# altimeter.net
KiCad netlist of a schematic drawn in EAGLE
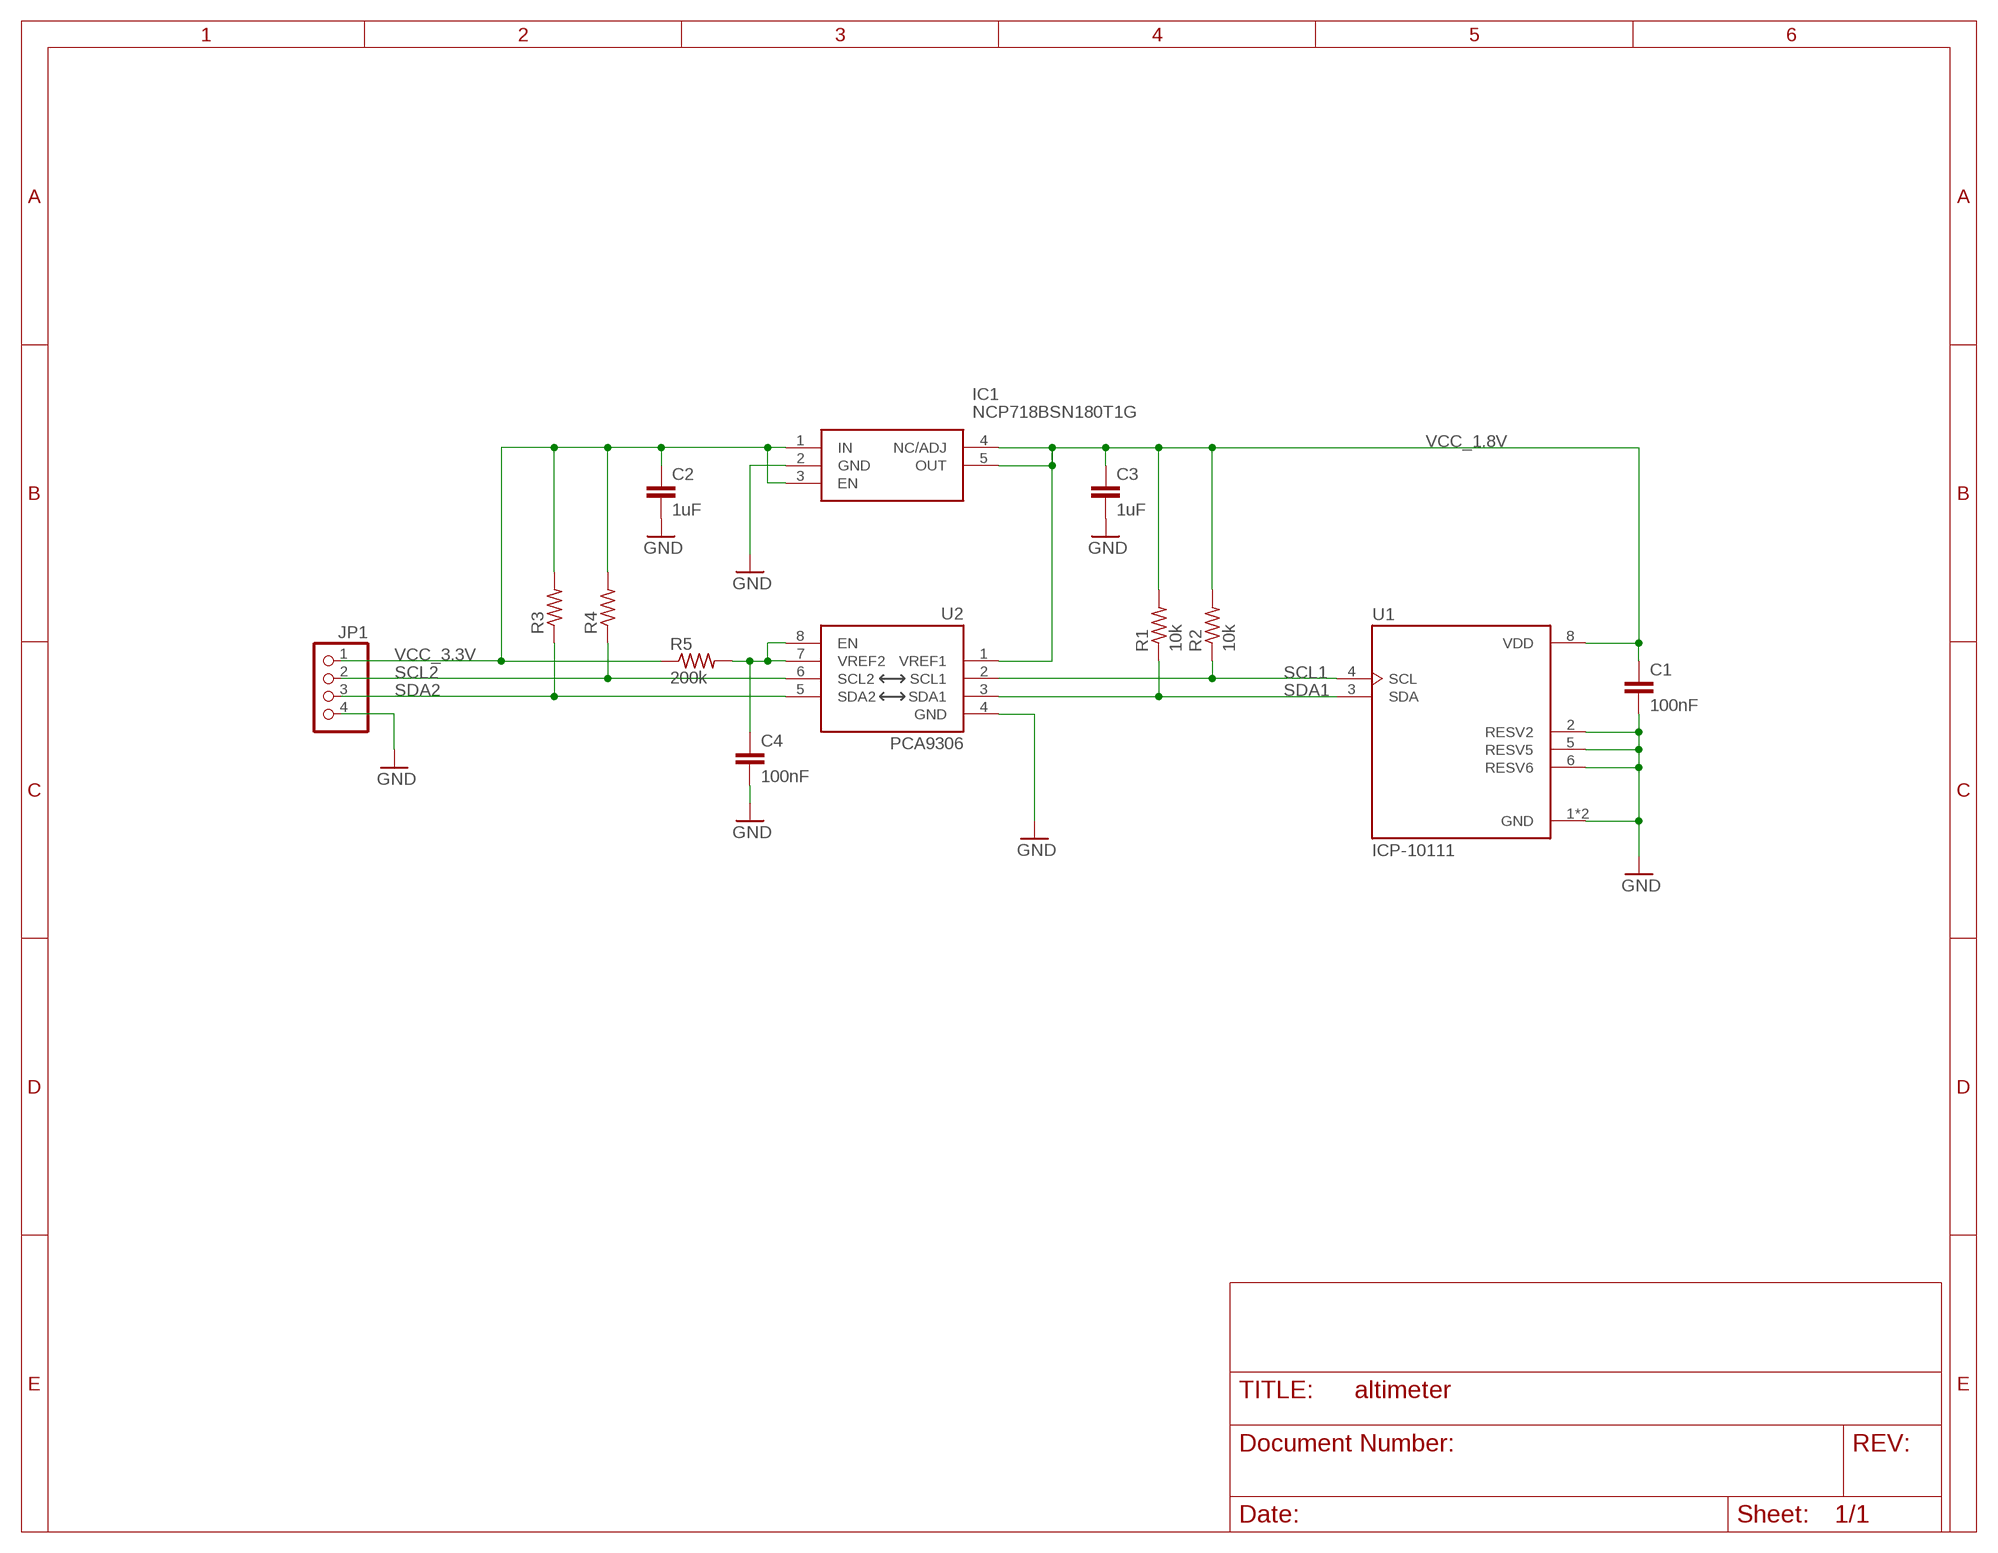
[diagram p0: schematic, sheet 1]

(export (version "E")
  (design (tool "Eeschema 10.0.6"))
  (components
    (comp (ref "C1")
      (value "100nF")
      (footprint "eagle-import:C0402")
      (libsource (lib "eagle-import") (part "C-EUC0402"))
    )
    (comp (ref "C2")
      (value "1uF")
      (footprint "eagle-import:C0402")
      (libsource (lib "eagle-import") (part "C-EUC0402"))
    )
    (comp (ref "C3")
      (value "1uF")
      (footprint "eagle-import:C0402")
      (libsource (lib "eagle-import") (part "C-EUC0402"))
    )
    (comp (ref "C4")
      (value "100nF")
      (footprint "eagle-import:C0402")
      (libsource (lib "eagle-import") (part "C-EUC0402"))
    )
    (comp (ref "IC1")
      (value "NCP718BSN180T1G")
      (footprint "eagle-import:SOT95P280X100-5N")
      (fields (field (name "MOUSER_PART_NUMBER") "863-NCP718BSN180T1G"))
      (libsource (lib "eagle-import") (part "NCP718BSN180T1G"))
    )
    (comp (ref "JP1")
      (value "PINHD-1X4")
      (footprint "eagle-import:1X04")
      (libsource (lib "eagle-import") (part "PINHD-1X4"))
    )
    (comp (ref "R1")
      (value "10k")
      (footprint "eagle-import:R0402")
      (libsource (lib "eagle-import") (part "R-US_R0402"))
    )
    (comp (ref "R2")
      (value "10k")
      (footprint "eagle-import:R0402")
      (libsource (lib "eagle-import") (part "R-US_R0402"))
    )
    (comp (ref "R3")
      (value "R-US_R0402")
      (footprint "eagle-import:R0402")
      (libsource (lib "eagle-import") (part "R-US_R0402"))
    )
    (comp (ref "R4")
      (value "R-US_R0402")
      (footprint "eagle-import:R0402")
      (libsource (lib "eagle-import") (part "R-US_R0402"))
    )
    (comp (ref "R5")
      (value "200k")
      (footprint "eagle-import:R0402")
      (libsource (lib "eagle-import") (part "R-US_R0402"))
    )
    (comp (ref "U1")
      (value "ICP-10111")
      (footprint "eagle-import:PSON65P250X200X100-8N")
      (fields (field (name "DIGI-KEY_PART_NUMBER") "1428-1145-1-ND") (field (name "MF") "TDK InvenSense"))
      (libsource (lib "eagle-import") (part "ICP-10111"))
    )
    (comp (ref "U2")
      (value "PCA9306")
      (footprint "eagle-import:PCA9306DC")
      (libsource (lib "eagle-import") (part "PCA9306PCA9306DC-1{colon}1"))
    )
  )
  (nets
    (net (code "1") (name "/SCL1") (class "Default")
      (node (ref "R2") (pin "1") (pinfunction "1_1") (pintype "passive"))
      (node (ref "U1") (pin "4") (pinfunction "SCL_4") (pintype "input"))
      (node (ref "U2") (pin "2") (pinfunction "SCL1_2") (pintype "bidirectional"))
    )
    (net (code "2") (name "/SCL2") (class "Default")
      (node (ref "JP1") (pin "2") (pinfunction "2_2") (pintype "passive"))
      (node (ref "R4") (pin "1") (pinfunction "1_1") (pintype "passive"))
      (node (ref "U2") (pin "6") (pinfunction "SCL2_6") (pintype "bidirectional"))
    )
    (net (code "3") (name "/SDA1") (class "Default")
      (node (ref "R1") (pin "1") (pinfunction "1_1") (pintype "passive"))
      (node (ref "U1") (pin "3") (pinfunction "SDA_3") (pintype "bidirectional"))
      (node (ref "U2") (pin "3") (pinfunction "SDA1_3") (pintype "bidirectional"))
    )
    (net (code "4") (name "/SDA2") (class "Default")
      (node (ref "JP1") (pin "3") (pinfunction "3_3") (pintype "passive"))
      (node (ref "R3") (pin "1") (pinfunction "1_1") (pintype "passive"))
      (node (ref "U2") (pin "5") (pinfunction "SDA2_5") (pintype "bidirectional"))
    )
    (net (code "5") (name "/VCC_1.8V") (class "Default")
      (node (ref "C1") (pin "1") (pinfunction "1_1") (pintype "passive"))
      (node (ref "C3") (pin "1") (pinfunction "1_1") (pintype "passive"))
      (node (ref "IC1") (pin "4") (pinfunction "NC/ADJ_4") (pintype "bidirectional"))
      (node (ref "IC1") (pin "5") (pinfunction "OUT_5") (pintype "bidirectional"))
      (node (ref "R1") (pin "2") (pinfunction "2_2") (pintype "passive"))
      (node (ref "R2") (pin "2") (pinfunction "2_2") (pintype "passive"))
      (node (ref "U1") (pin "8") (pinfunction "VDD_8") (pintype "power_in"))
      (node (ref "U2") (pin "1") (pinfunction "VREF1_1") (pintype "bidirectional"))
    )
    (net (code "6") (name "/VCC_3.3V") (class "Default")
      (node (ref "C2") (pin "1") (pinfunction "1_1") (pintype "passive"))
      (node (ref "IC1") (pin "1") (pinfunction "IN_1") (pintype "bidirectional"))
      (node (ref "IC1") (pin "3") (pinfunction "EN_3") (pintype "bidirectional"))
      (node (ref "JP1") (pin "1") (pinfunction "1_1") (pintype "passive"))
      (node (ref "R3") (pin "2") (pinfunction "2_2") (pintype "passive"))
      (node (ref "R4") (pin "2") (pinfunction "2_2") (pintype "passive"))
      (node (ref "R5") (pin "1") (pinfunction "1_1") (pintype "passive"))
    )
    (net (code "7") (name "GND") (class "Default")
      (node (ref "C1") (pin "2") (pinfunction "2_2") (pintype "passive"))
      (node (ref "C2") (pin "2") (pinfunction "2_2") (pintype "passive"))
      (node (ref "C3") (pin "2") (pinfunction "2_2") (pintype "passive"))
      (node (ref "C4") (pin "2") (pinfunction "2_2") (pintype "passive"))
      (node (ref "IC1") (pin "2") (pinfunction "GND_2") (pintype "bidirectional"))
      (node (ref "JP1") (pin "4") (pinfunction "4_4") (pintype "passive"))
      (node (ref "U1") (pin "1") (pinfunction "GND_1") (pintype "power_in"))
      (node (ref "U1") (pin "2") (pinfunction "RESV2_2") (pintype "passive"))
      (node (ref "U1") (pin "5") (pinfunction "RESV5_5") (pintype "passive"))
      (node (ref "U1") (pin "6") (pinfunction "RESV6_6") (pintype "passive"))
      (node (ref "U1") (pin "7") (pinfunction "GND_7") (pintype "power_in"))
      (node (ref "U2") (pin "4") (pinfunction "GND_4") (pintype "bidirectional"))
    )
    (net (code "8") (name "Net-(U2-EN)") (class "Default")
      (node (ref "C4") (pin "1") (pinfunction "1_1") (pintype "passive"))
      (node (ref "R5") (pin "2") (pinfunction "2_2") (pintype "passive"))
      (node (ref "U2") (pin "7") (pinfunction "VREF2_7") (pintype "bidirectional"))
      (node (ref "U2") (pin "8") (pinfunction "EN_8") (pintype "bidirectional"))
    )
  )
)
